# esp32-canbus.net
KiCad netlist of a schematic drawn in EAGLE
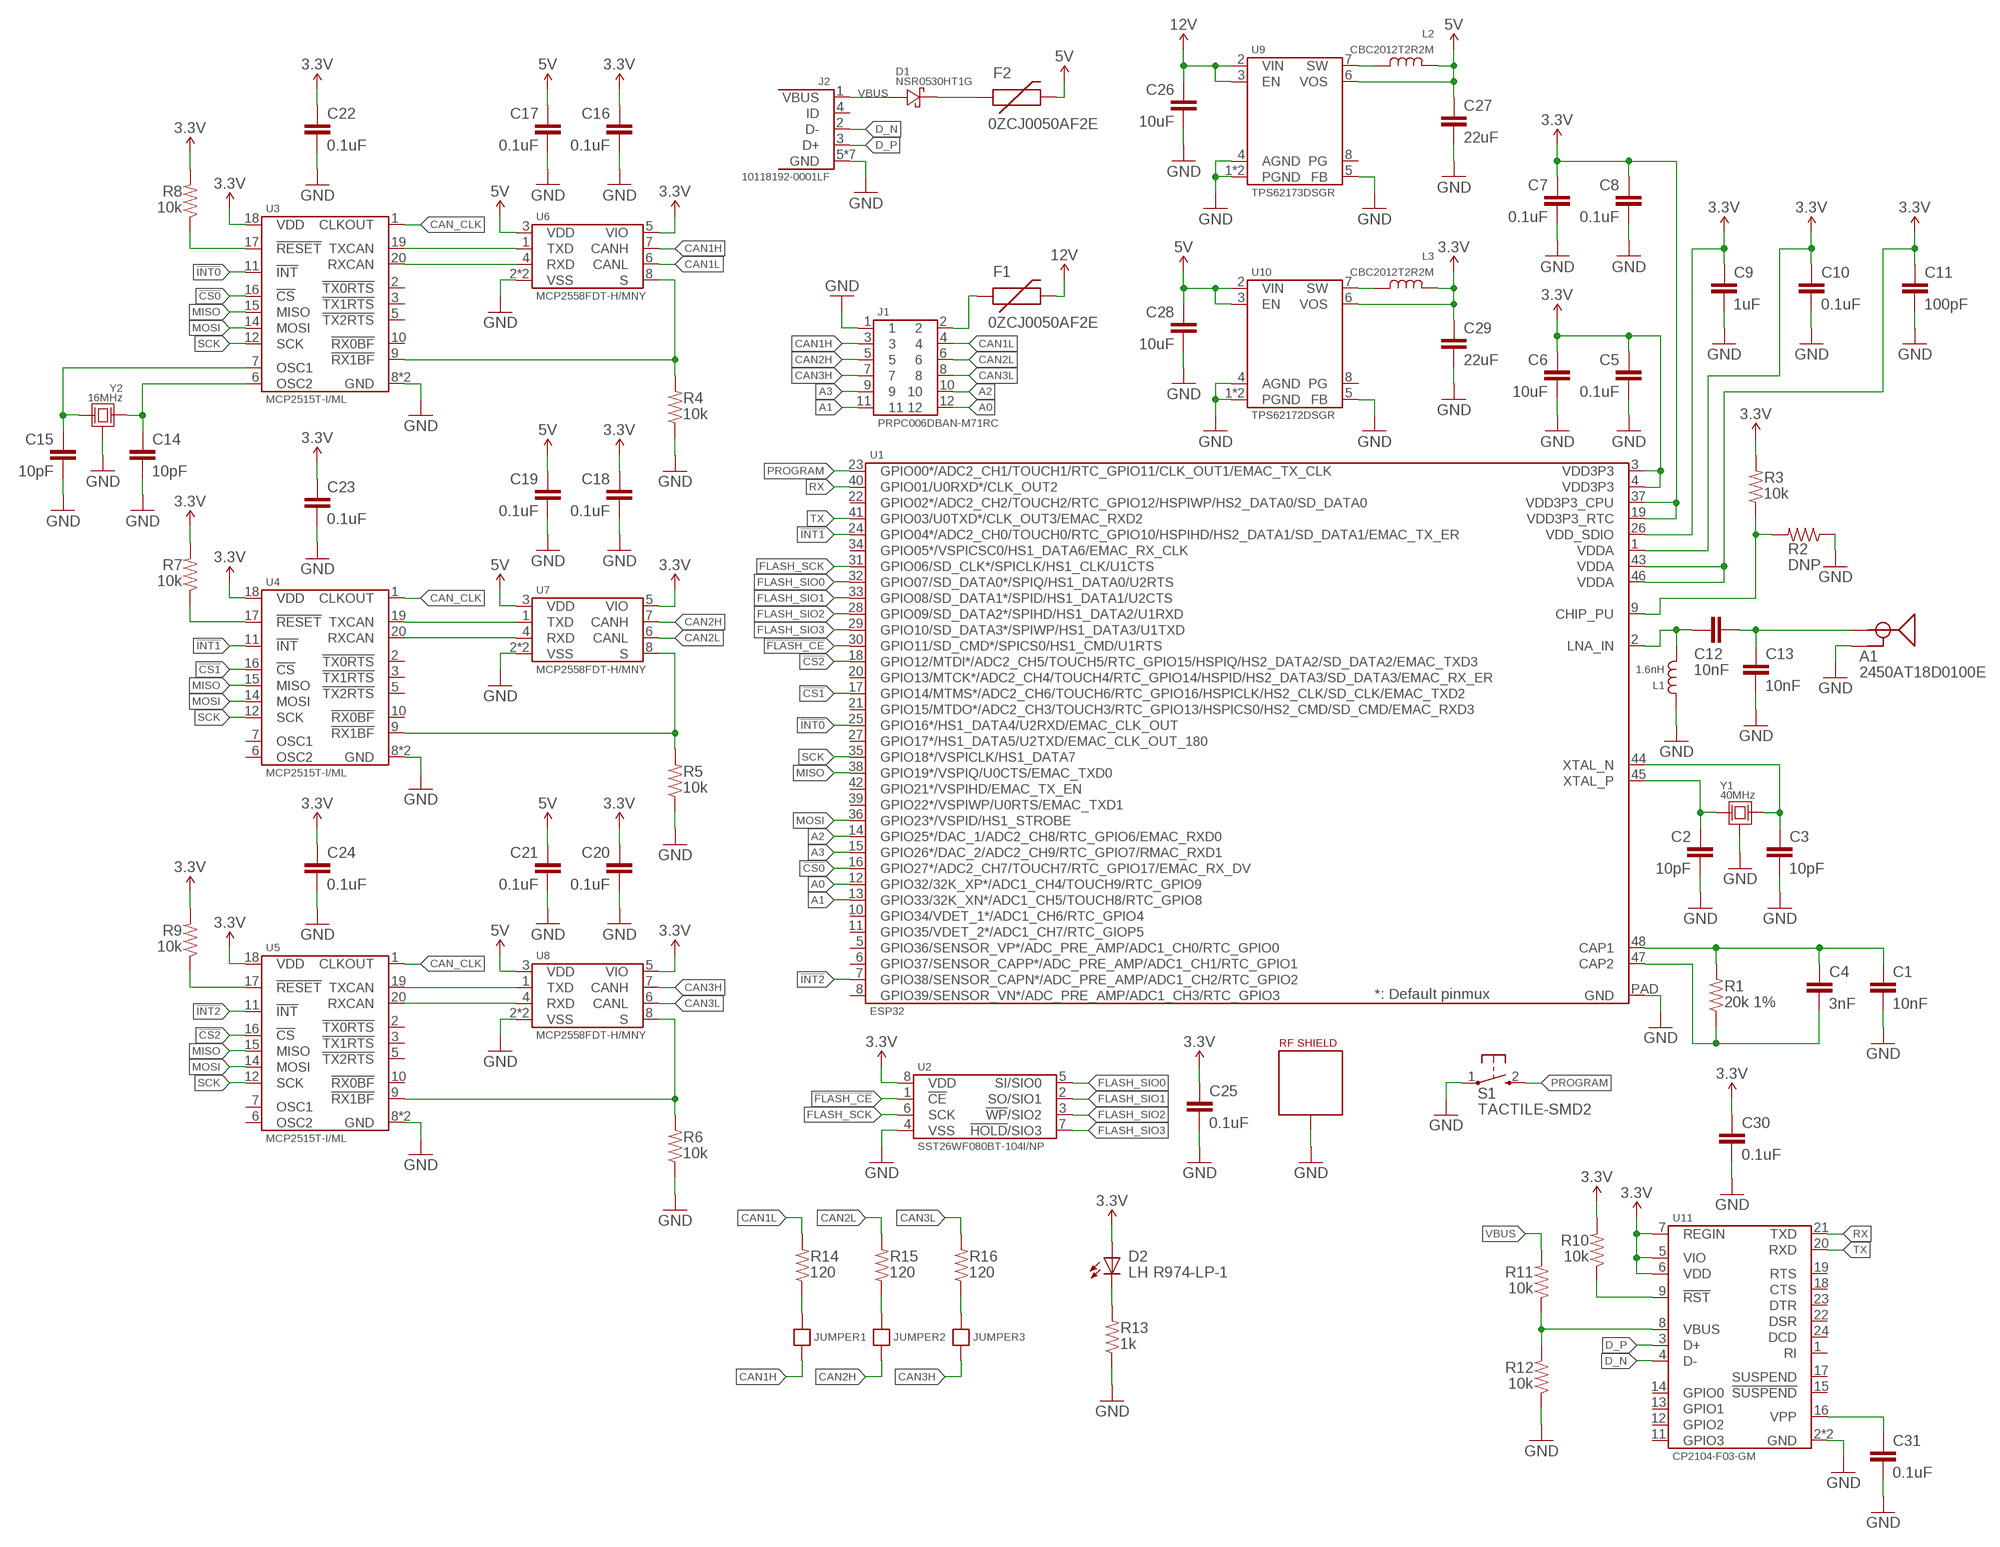
[diagram p0: schematic, sheet 1]

(export (version "E")
  (design (tool "Eeschema 10.0.6"))
  (components
    (comp (ref "A1")
      (value "2450AT18D0100E")
      (footprint "eagle-import:4SMD-ANTENNA")
      (libsource (lib "eagle-import") (part "2450AT18D0100E"))
    )
    (comp (ref "C1")
      (value "10nF")
      (footprint "eagle-import:0603-CAP")
      (libsource (lib "eagle-import") (part "CAP-0603"))
    )
    (comp (ref "C2")
      (value "10pF")
      (footprint "eagle-import:0603-CAP")
      (libsource (lib "eagle-import") (part "CAP-0603"))
    )
    (comp (ref "C3")
      (value "10pF")
      (footprint "eagle-import:0603-CAP")
      (libsource (lib "eagle-import") (part "CAP-0603"))
    )
    (comp (ref "C4")
      (value "3nF")
      (footprint "eagle-import:0603-CAP")
      (libsource (lib "eagle-import") (part "CAP-0603"))
    )
    (comp (ref "C5")
      (value "0.1uF")
      (footprint "eagle-import:0603-CAP")
      (libsource (lib "eagle-import") (part "CAP-0603"))
    )
    (comp (ref "C6")
      (value "10uF")
      (footprint "eagle-import:0603-CAP")
      (libsource (lib "eagle-import") (part "CAP-0603"))
    )
    (comp (ref "C7")
      (value "0.1uF")
      (footprint "eagle-import:0603-CAP")
      (libsource (lib "eagle-import") (part "CAP-0603"))
    )
    (comp (ref "C8")
      (value "0.1uF")
      (footprint "eagle-import:0603-CAP")
      (libsource (lib "eagle-import") (part "CAP-0603"))
    )
    (comp (ref "C9")
      (value "1uF")
      (footprint "eagle-import:0603-CAP")
      (libsource (lib "eagle-import") (part "CAP-0603"))
    )
    (comp (ref "C10")
      (value "0.1uF")
      (footprint "eagle-import:0603-CAP")
      (libsource (lib "eagle-import") (part "CAP-0603"))
    )
    (comp (ref "C11")
      (value "100pF")
      (footprint "eagle-import:0603-CAP")
      (libsource (lib "eagle-import") (part "CAP-0603"))
    )
    (comp (ref "C12")
      (value "10nF")
      (footprint "eagle-import:0603-CAP")
      (libsource (lib "eagle-import") (part "CAP-0603"))
    )
    (comp (ref "C13")
      (value "10nF")
      (footprint "eagle-import:0603-CAP")
      (libsource (lib "eagle-import") (part "CAP-0603"))
    )
    (comp (ref "C14")
      (value "10pF")
      (footprint "eagle-import:0603-CAP")
      (libsource (lib "eagle-import") (part "CAP-0603"))
    )
    (comp (ref "C15")
      (value "10pF")
      (footprint "eagle-import:0603-CAP")
      (libsource (lib "eagle-import") (part "CAP-0603"))
    )
    (comp (ref "C16")
      (value "0.1uF")
      (footprint "eagle-import:0603-CAP")
      (libsource (lib "eagle-import") (part "CAP-0603"))
    )
    (comp (ref "C17")
      (value "0.1uF")
      (footprint "eagle-import:0603-CAP")
      (libsource (lib "eagle-import") (part "CAP-0603"))
    )
    (comp (ref "C18")
      (value "0.1uF")
      (footprint "eagle-import:0603-CAP")
      (libsource (lib "eagle-import") (part "CAP-0603"))
    )
    (comp (ref "C19")
      (value "0.1uF")
      (footprint "eagle-import:0603-CAP")
      (libsource (lib "eagle-import") (part "CAP-0603"))
    )
    (comp (ref "C20")
      (value "0.1uF")
      (footprint "eagle-import:0603-CAP")
      (libsource (lib "eagle-import") (part "CAP-0603"))
    )
    (comp (ref "C21")
      (value "0.1uF")
      (footprint "eagle-import:0603-CAP")
      (libsource (lib "eagle-import") (part "CAP-0603"))
    )
    (comp (ref "C22")
      (value "0.1uF")
      (footprint "eagle-import:0603-CAP")
      (libsource (lib "eagle-import") (part "CAP-0603"))
    )
    (comp (ref "C23")
      (value "0.1uF")
      (footprint "eagle-import:0603-CAP")
      (libsource (lib "eagle-import") (part "CAP-0603"))
    )
    (comp (ref "C24")
      (value "0.1uF")
      (footprint "eagle-import:0603-CAP")
      (libsource (lib "eagle-import") (part "CAP-0603"))
    )
    (comp (ref "C25")
      (value "0.1uF")
      (footprint "eagle-import:0603-CAP")
      (libsource (lib "eagle-import") (part "CAP-0603"))
    )
    (comp (ref "C26")
      (value "10uF")
      (footprint "eagle-import:0603-CAP")
      (libsource (lib "eagle-import") (part "CAP-0603"))
    )
    (comp (ref "C27")
      (value "22uF")
      (footprint "eagle-import:0805-CAP")
      (libsource (lib "eagle-import") (part "CAP-0805"))
    )
    (comp (ref "C28")
      (value "10uF")
      (footprint "eagle-import:0603-CAP")
      (libsource (lib "eagle-import") (part "CAP-0603"))
    )
    (comp (ref "C29")
      (value "22uF")
      (footprint "eagle-import:0805-CAP")
      (libsource (lib "eagle-import") (part "CAP-0805"))
    )
    (comp (ref "C30")
      (value "0.1uF")
      (footprint "eagle-import:0603-CAP")
      (libsource (lib "eagle-import") (part "CAP-0603"))
    )
    (comp (ref "C31")
      (value "0.1uF")
      (footprint "eagle-import:0603-CAP")
      (libsource (lib "eagle-import") (part "CAP-0603"))
    )
    (comp (ref "D1")
      (value "NSR0530HT1G")
      (footprint "eagle-import:SOD323")
      (libsource (lib "eagle-import") (part "NSR0530HT1G"))
    )
    (comp (ref "D2")
      (value "LH R974-LP-1")
      (footprint "eagle-import:0805-LED")
      (libsource (lib "eagle-import") (part "LED-0805"))
    )
    (comp (ref "F1")
      (value "0ZCJ0050AF2E")
      (footprint "eagle-import:1206-PTC")
      (libsource (lib "eagle-import") (part "PTC-1206"))
    )
    (comp (ref "F2")
      (value "0ZCJ0050AF2E")
      (footprint "eagle-import:1206-PTC")
      (libsource (lib "eagle-import") (part "PTC-1206"))
    )
    (comp (ref "J1")
      (value "PRPC006DBAN-M71RC")
      (footprint "eagle-import:M06X2-PTH-H")
      (libsource (lib "eagle-import") (part "M06X2-100MIL-H"))
    )
    (comp (ref "J2")
      (value "10118192-0001LF")
      (footprint "eagle-import:10118192-0001LF")
      (libsource (lib "eagle-import") (part "USB-MICROB-3"))
    )
    (comp (ref "JUMPER1")
      (value "JUMPER-NO")
      (footprint "eagle-import:JUMPER-NO")
      (libsource (lib "eagle-import") (part "JUMPER-NO"))
    )
    (comp (ref "JUMPER2")
      (value "JUMPER-NO")
      (footprint "eagle-import:JUMPER-NO")
      (libsource (lib "eagle-import") (part "JUMPER-NO"))
    )
    (comp (ref "JUMPER3")
      (value "JUMPER-NO")
      (footprint "eagle-import:JUMPER-NO")
      (libsource (lib "eagle-import") (part "JUMPER-NO"))
    )
    (comp (ref "L1")
      (value "1.6nH")
      (footprint "eagle-import:0402-INDUCTOR")
      (libsource (lib "eagle-import") (part "INDUCTOR-0402"))
    )
    (comp (ref "L2")
      (value "CBC2012T2R2M")
      (footprint "eagle-import:0805")
      (libsource (lib "eagle-import") (part "INDUCTOR-0805"))
    )
    (comp (ref "L3")
      (value "CBC2012T2R2M")
      (footprint "eagle-import:0805")
      (libsource (lib "eagle-import") (part "INDUCTOR-0805"))
    )
    (comp (ref "R1")
      (value "20k 1%")
      (footprint "eagle-import:0603-CAP")
      (libsource (lib "eagle-import") (part "RESISTOR-0603"))
    )
    (comp (ref "R2")
      (value "DNP")
      (footprint "eagle-import:0603-CAP")
      (libsource (lib "eagle-import") (part "RESISTOR-0603"))
    )
    (comp (ref "R3")
      (value "10k")
      (footprint "eagle-import:0603-CAP")
      (libsource (lib "eagle-import") (part "RESISTOR-0603"))
    )
    (comp (ref "R4")
      (value "10k")
      (footprint "eagle-import:0603-CAP")
      (libsource (lib "eagle-import") (part "RESISTOR-0603"))
    )
    (comp (ref "R5")
      (value "10k")
      (footprint "eagle-import:0603-CAP")
      (libsource (lib "eagle-import") (part "RESISTOR-0603"))
    )
    (comp (ref "R6")
      (value "10k")
      (footprint "eagle-import:0603-CAP")
      (libsource (lib "eagle-import") (part "RESISTOR-0603"))
    )
    (comp (ref "R7")
      (value "10k")
      (footprint "eagle-import:0603-CAP")
      (libsource (lib "eagle-import") (part "RESISTOR-0603"))
    )
    (comp (ref "R8")
      (value "10k")
      (footprint "eagle-import:0603-CAP")
      (libsource (lib "eagle-import") (part "RESISTOR-0603"))
    )
    (comp (ref "R9")
      (value "10k")
      (footprint "eagle-import:0603-CAP")
      (libsource (lib "eagle-import") (part "RESISTOR-0603"))
    )
    (comp (ref "R10")
      (value "10k")
      (footprint "eagle-import:0603-CAP")
      (libsource (lib "eagle-import") (part "RESISTOR-0603"))
    )
    (comp (ref "R11")
      (value "10k")
      (footprint "eagle-import:0603-CAP")
      (libsource (lib "eagle-import") (part "RESISTOR-0603"))
    )
    (comp (ref "R12")
      (value "10k")
      (footprint "eagle-import:0603-CAP")
      (libsource (lib "eagle-import") (part "RESISTOR-0603"))
    )
    (comp (ref "R13")
      (value "1k")
      (footprint "eagle-import:0603-CAP")
      (libsource (lib "eagle-import") (part "RESISTOR-0603"))
    )
    (comp (ref "R14")
      (value "120")
      (footprint "eagle-import:0603-CAP")
      (libsource (lib "eagle-import") (part "RESISTOR-0603"))
    )
    (comp (ref "R15")
      (value "120")
      (footprint "eagle-import:0603-CAP")
      (libsource (lib "eagle-import") (part "RESISTOR-0603"))
    )
    (comp (ref "R16")
      (value "120")
      (footprint "eagle-import:0603-CAP")
      (libsource (lib "eagle-import") (part "RESISTOR-0603"))
    )
    (comp (ref "S1")
      (value "TACTILE-SMD2")
      (footprint "eagle-import:PTS820-J15M-SMTR-LFS")
      (libsource (lib "eagle-import") (part "TACTILE-SMD2"))
    )
    (comp (ref "SH1")
      (value "BMI-S-102")
      (footprint "eagle-import:RF_SHIELD-.65X.65")
      (libsource (lib "eagle-import") (part "RF-SHIELD"))
    )
    (comp (ref "U1")
      (value "ESP32")
      (footprint "eagle-import:ESP32")
      (libsource (lib "eagle-import") (part "ESP32"))
    )
    (comp (ref "U2")
      (value "SST26WF080BT-104I/NP")
      (footprint "eagle-import:USON-8-2X3")
      (libsource (lib "eagle-import") (part "FLASH-USON"))
    )
    (comp (ref "U3")
      (value "MCP2515T-I/ML")
      (footprint "eagle-import:VQFN-20-4MM")
      (libsource (lib "eagle-import") (part "MCP2515T-I/ML"))
    )
    (comp (ref "U4")
      (value "MCP2515T-I/ML")
      (footprint "eagle-import:VQFN-20-4MM")
      (libsource (lib "eagle-import") (part "MCP2515T-I/ML"))
    )
    (comp (ref "U5")
      (value "MCP2515T-I/ML")
      (footprint "eagle-import:VQFN-20-4MM")
      (libsource (lib "eagle-import") (part "MCP2515T-I/ML"))
    )
    (comp (ref "U6")
      (value "MCP2558FDT-H/MNY")
      (footprint "eagle-import:TDFN-8-2X3")
      (libsource (lib "eagle-import") (part "MCP2558FDT-H/MNY"))
    )
    (comp (ref "U7")
      (value "MCP2558FDT-H/MNY")
      (footprint "eagle-import:TDFN-8-2X3")
      (libsource (lib "eagle-import") (part "MCP2558FDT-H/MNY"))
    )
    (comp (ref "U8")
      (value "MCP2558FDT-H/MNY")
      (footprint "eagle-import:TDFN-8-2X3")
      (libsource (lib "eagle-import") (part "MCP2558FDT-H/MNY"))
    )
    (comp (ref "U9")
      (value "TPS62173DSGR")
      (footprint "eagle-import:DFN-8-2MM")
      (libsource (lib "eagle-import") (part "TPS62173DSGR"))
    )
    (comp (ref "U10")
      (value "TPS62172DSGR")
      (footprint "eagle-import:DFN-8-2MM")
      (libsource (lib "eagle-import") (part "TPS62172DSGR"))
    )
    (comp (ref "U11")
      (value "CP2104-F03-GM")
      (footprint "eagle-import:QFN-24-4X4")
      (libsource (lib "eagle-import") (part "CP2104-F03-GM"))
    )
    (comp (ref "Y1")
      (value "40MHz")
      (footprint "eagle-import:FA-238")
      (libsource (lib "eagle-import") (part "CRYSTAL-3.2X2.5"))
    )
    (comp (ref "Y2")
      (value "16MHz")
      (footprint "eagle-import:FA-238")
      (libsource (lib "eagle-import") (part "CRYSTAL-3.2X2.5"))
    )
  )
  (nets
    (net (code "1") (name "/~{CS0}") (class "Default")
      (node (ref "U1") (pin "16") (pinfunction "GPIO27*/ADC2_CH7/TOUCH7/RTC_GPIO17/EMAC_RX_DV_16") (pintype "bidirectional"))
      (node (ref "U3") (pin "16") (pinfunction "~{CS}_16") (pintype "bidirectional"))
    )
    (net (code "2") (name "/~{CS1}") (class "Default")
      (node (ref "U1") (pin "17") (pinfunction "GPIO14/MTMS*/ADC2_CH6/TOUCH6/RTC_GPIO16/HSPICLK/HS2_CLK/SD_CLK/EMAC_TXD2_17") (pintype "bidirectional"))
      (node (ref "U4") (pin "16") (pinfunction "~{CS}_16") (pintype "bidirectional"))
    )
    (net (code "3") (name "/~{CS2}") (class "Default")
      (node (ref "U1") (pin "18") (pinfunction "GPIO12/MTDI*/ADC2_CH5/TOUCH5/RTC_GPIO15/HSPIQ/HS2_DATA2/SD_DATA2/EMAC_TXD3_18") (pintype "bidirectional"))
      (node (ref "U5") (pin "16") (pinfunction "~{CS}_16") (pintype "bidirectional"))
    )
    (net (code "4") (name "/~{FLASH_CE}") (class "Default")
      (node (ref "U1") (pin "30") (pinfunction "GPIO11/SD_CMD*/SPICS0/HS1_CMD/U1RTS_30") (pintype "bidirectional"))
      (node (ref "U2") (pin "1") (pinfunction "~{CE}_1") (pintype "bidirectional"))
    )
    (net (code "5") (name "/~{INT0}") (class "Default")
      (node (ref "U1") (pin "25") (pinfunction "GPIO16*/HS1_DATA4/U2RXD/EMAC_CLK_OUT_25") (pintype "bidirectional"))
      (node (ref "U3") (pin "11") (pinfunction "~{INT}_11") (pintype "bidirectional"))
    )
    (net (code "6") (name "/~{INT1}") (class "Default")
      (node (ref "U1") (pin "24") (pinfunction "GPIO04*/ADC2_CH0/TOUCH0/RTC_GPIO10/HSPIHD/HS2_DATA1/SD_DATA1/EMAC_TX_ER_24") (pintype "bidirectional"))
      (node (ref "U4") (pin "11") (pinfunction "~{INT}_11") (pintype "bidirectional"))
    )
    (net (code "7") (name "/~{INT2}") (class "Default")
      (node (ref "U1") (pin "7") (pinfunction "GPIO38/SENSOR_CAPN*/ADC_PRE_AMP/ADC1_CH2/RTC_GPIO2_7") (pintype "bidirectional"))
      (node (ref "U5") (pin "11") (pinfunction "~{INT}_11") (pintype "bidirectional"))
    )
    (net (code "8") (name "3.3V") (class "Default")
      (node (ref "C10") (pin "1") (pinfunction "1_1") (pintype "passive"))
      (node (ref "C11") (pin "1") (pinfunction "1_1") (pintype "passive"))
      (node (ref "C16") (pin "1") (pinfunction "1_1") (pintype "passive"))
      (node (ref "C18") (pin "1") (pinfunction "1_1") (pintype "passive"))
      (node (ref "C20") (pin "1") (pinfunction "1_1") (pintype "passive"))
      (node (ref "C22") (pin "1") (pinfunction "1_1") (pintype "passive"))
      (node (ref "C23") (pin "1") (pinfunction "1_1") (pintype "passive"))
      (node (ref "C24") (pin "1") (pinfunction "1_1") (pintype "passive"))
      (node (ref "C25") (pin "1") (pinfunction "1_1") (pintype "passive"))
      (node (ref "C29") (pin "1") (pinfunction "1_1") (pintype "passive"))
      (node (ref "C30") (pin "1") (pinfunction "1_1") (pintype "passive"))
      (node (ref "C5") (pin "1") (pinfunction "1_1") (pintype "passive"))
      (node (ref "C6") (pin "1") (pinfunction "1_1") (pintype "passive"))
      (node (ref "C7") (pin "1") (pinfunction "1_1") (pintype "passive"))
      (node (ref "C8") (pin "1") (pinfunction "1_1") (pintype "passive"))
      (node (ref "C9") (pin "1") (pinfunction "1_1") (pintype "passive"))
      (node (ref "D2") (pin "A") (pinfunction "A_A") (pintype "passive"))
      (node (ref "L3") (pin "2") (pinfunction "P$2_2") (pintype "bidirectional"))
      (node (ref "R10") (pin "2") (pinfunction "2_2") (pintype "passive"))
      (node (ref "R3") (pin "2") (pinfunction "2_2") (pintype "passive"))
      (node (ref "R7") (pin "2") (pinfunction "2_2") (pintype "passive"))
      (node (ref "R8") (pin "2") (pinfunction "2_2") (pintype "passive"))
      (node (ref "R9") (pin "2") (pinfunction "2_2") (pintype "passive"))
      (node (ref "U1") (pin "1") (pinfunction "VDDA_1") (pintype "bidirectional"))
      (node (ref "U1") (pin "19") (pinfunction "VDD3P3_RTC_19") (pintype "bidirectional"))
      (node (ref "U1") (pin "26") (pinfunction "VDD_SDIO_26") (pintype "bidirectional"))
      (node (ref "U1") (pin "3") (pinfunction "VDD3P3_3") (pintype "bidirectional"))
      (node (ref "U1") (pin "37") (pinfunction "VDD3P3_CPU_37") (pintype "bidirectional"))
      (node (ref "U1") (pin "4") (pinfunction "VDD3P3_4") (pintype "bidirectional"))
      (node (ref "U1") (pin "43") (pinfunction "VDDA_43") (pintype "bidirectional"))
      (node (ref "U1") (pin "46") (pinfunction "VDDA_46") (pintype "bidirectional"))
      (node (ref "U10") (pin "6") (pinfunction "VOS_6") (pintype "bidirectional"))
      (node (ref "U11") (pin "5") (pinfunction "VIO_5") (pintype "bidirectional"))
      (node (ref "U11") (pin "6") (pinfunction "VDD_6") (pintype "bidirectional"))
      (node (ref "U11") (pin "7") (pinfunction "REGIN_7") (pintype "bidirectional"))
      (node (ref "U2") (pin "8") (pinfunction "VDD_8") (pintype "bidirectional"))
      (node (ref "U3") (pin "18") (pinfunction "VDD_18") (pintype "bidirectional"))
      (node (ref "U4") (pin "18") (pinfunction "VDD_18") (pintype "bidirectional"))
      (node (ref "U5") (pin "18") (pinfunction "VDD_18") (pintype "bidirectional"))
      (node (ref "U6") (pin "5") (pinfunction "VIO_5") (pintype "bidirectional"))
      (node (ref "U7") (pin "5") (pinfunction "VIO_5") (pintype "bidirectional"))
      (node (ref "U8") (pin "5") (pinfunction "VIO_5") (pintype "bidirectional"))
    )
    (net (code "9") (name "5V") (class "Default")
      (node (ref "C17") (pin "1") (pinfunction "1_1") (pintype "passive"))
      (node (ref "C19") (pin "1") (pinfunction "1_1") (pintype "passive"))
      (node (ref "C21") (pin "1") (pinfunction "1_1") (pintype "passive"))
      (node (ref "C27") (pin "1") (pinfunction "1_1") (pintype "passive"))
      (node (ref "C28") (pin "1") (pinfunction "1_1") (pintype "passive"))
      (node (ref "F2") (pin "P$2") (pinfunction "2_P$2") (pintype "bidirectional"))
      (node (ref "L2") (pin "2") (pinfunction "P$2_2") (pintype "bidirectional"))
      (node (ref "U10") (pin "2") (pinfunction "VIN_2") (pintype "bidirectional"))
      (node (ref "U10") (pin "3") (pinfunction "EN_3") (pintype "bidirectional"))
      (node (ref "U6") (pin "3") (pinfunction "VDD_3") (pintype "bidirectional"))
      (node (ref "U7") (pin "3") (pinfunction "VDD_3") (pintype "bidirectional"))
      (node (ref "U8") (pin "3") (pinfunction "VDD_3") (pintype "bidirectional"))
      (node (ref "U9") (pin "6") (pinfunction "VOS_6") (pintype "bidirectional"))
    )
    (net (code "10") (name "12V") (class "Default")
      (node (ref "C26") (pin "1") (pinfunction "1_1") (pintype "passive"))
      (node (ref "F1") (pin "P$2") (pinfunction "2_P$2") (pintype "bidirectional"))
      (node (ref "U9") (pin "2") (pinfunction "VIN_2") (pintype "bidirectional"))
      (node (ref "U9") (pin "3") (pinfunction "EN_3") (pintype "bidirectional"))
    )
    (net (code "11") (name "A0") (class "Default")
      (node (ref "J1") (pin "12") (pinfunction "12_12") (pintype "bidirectional"))
      (node (ref "U1") (pin "12") (pinfunction "GPIO32/32K_XP*/ADC1_CH4/TOUCH9/RTC_GPIO9_12") (pintype "bidirectional"))
    )
    (net (code "12") (name "A1") (class "Default")
      (node (ref "J1") (pin "11") (pinfunction "11_11") (pintype "bidirectional"))
      (node (ref "U1") (pin "13") (pinfunction "GPIO33/32K_XN*/ADC1_CH5/TOUCH8/RTC_GPIO8_13") (pintype "bidirectional"))
    )
    (net (code "13") (name "A2") (class "Default")
      (node (ref "J1") (pin "10") (pinfunction "10_10") (pintype "bidirectional"))
      (node (ref "U1") (pin "14") (pinfunction "GPIO25*/DAC_1/ADC2_CH8/RTC_GPIO6/EMAC_RXD0_14") (pintype "bidirectional"))
    )
    (net (code "14") (name "A3") (class "Default")
      (node (ref "J1") (pin "9") (pinfunction "9_9") (pintype "bidirectional"))
      (node (ref "U1") (pin "15") (pinfunction "GPIO26*/DAC_2/ADC2_CH9/RTC_GPIO7/RMAC_RXD1_15") (pintype "bidirectional"))
    )
    (net (code "15") (name "CAN1H") (class "Default")
      (node (ref "J1") (pin "3") (pinfunction "3_3") (pintype "bidirectional"))
      (node (ref "JUMPER1") (pin "P$1") (pinfunction "P$1_P$1") (pintype "bidirectional"))
      (node (ref "U6") (pin "7") (pinfunction "CANH_7") (pintype "bidirectional"))
    )
    (net (code "16") (name "CAN1L") (class "Default")
      (node (ref "J1") (pin "4") (pinfunction "4_4") (pintype "bidirectional"))
      (node (ref "R14") (pin "2") (pinfunction "2_2") (pintype "passive"))
      (node (ref "U6") (pin "6") (pinfunction "CANL_6") (pintype "bidirectional"))
    )
    (net (code "17") (name "CAN2H") (class "Default")
      (node (ref "J1") (pin "5") (pinfunction "5_5") (pintype "bidirectional"))
      (node (ref "JUMPER2") (pin "P$1") (pinfunction "P$1_P$1") (pintype "bidirectional"))
      (node (ref "U7") (pin "7") (pinfunction "CANH_7") (pintype "bidirectional"))
    )
    (net (code "18") (name "CAN2L") (class "Default")
      (node (ref "J1") (pin "6") (pinfunction "6_6") (pintype "bidirectional"))
      (node (ref "R15") (pin "2") (pinfunction "2_2") (pintype "passive"))
      (node (ref "U7") (pin "6") (pinfunction "CANL_6") (pintype "bidirectional"))
    )
    (net (code "19") (name "CAN3H") (class "Default")
      (node (ref "J1") (pin "7") (pinfunction "7_7") (pintype "bidirectional"))
      (node (ref "JUMPER3") (pin "P$1") (pinfunction "P$1_P$1") (pintype "bidirectional"))
      (node (ref "U8") (pin "7") (pinfunction "CANH_7") (pintype "bidirectional"))
    )
    (net (code "20") (name "CAN3L") (class "Default")
      (node (ref "J1") (pin "8") (pinfunction "8_8") (pintype "bidirectional"))
      (node (ref "R16") (pin "2") (pinfunction "2_2") (pintype "passive"))
      (node (ref "U8") (pin "6") (pinfunction "CANL_6") (pintype "bidirectional"))
    )
    (net (code "21") (name "CAN_CLK") (class "Default")
      (node (ref "U3") (pin "1") (pinfunction "CLKOUT_1") (pintype "bidirectional"))
      (node (ref "U4") (pin "1") (pinfunction "CLKOUT_1") (pintype "bidirectional"))
      (node (ref "U5") (pin "1") (pinfunction "CLKOUT_1") (pintype "bidirectional"))
    )
    (net (code "22") (name "D_N") (class "Default")
      (node (ref "J2") (pin "2") (pinfunction "D-_2") (pintype "bidirectional"))
      (node (ref "U11") (pin "4") (pinfunction "D-_4") (pintype "bidirectional"))
    )
    (net (code "23") (name "D_P") (class "Default")
      (node (ref "J2") (pin "3") (pinfunction "D+_3") (pintype "bidirectional"))
      (node (ref "U11") (pin "3") (pinfunction "D+_3") (pintype "bidirectional"))
    )
    (net (code "24") (name "FLASH_SCK") (class "Default")
      (node (ref "U1") (pin "31") (pinfunction "GPIO06/SD_CLK*/SPICLK/HS1_CLK/U1CTS_31") (pintype "bidirectional"))
      (node (ref "U2") (pin "6") (pinfunction "SCK_6") (pintype "bidirectional"))
    )
    (net (code "25") (name "FLASH_SIO0") (class "Default")
      (node (ref "U1") (pin "32") (pinfunction "GPIO07/SD_DATA0*/SPIQ/HS1_DATA0/U2RTS_32") (pintype "bidirectional"))
      (node (ref "U2") (pin "5") (pinfunction "SI/SIO0_5") (pintype "bidirectional"))
    )
    (net (code "26") (name "FLASH_SIO1") (class "Default")
      (node (ref "U1") (pin "33") (pinfunction "GPIO08/SD_DATA1*/SPID/HS1_DATA1/U2CTS_33") (pintype "bidirectional"))
      (node (ref "U2") (pin "2") (pinfunction "SO/SIO1_2") (pintype "bidirectional"))
    )
    (net (code "27") (name "FLASH_SIO2") (class "Default")
      (node (ref "U1") (pin "28") (pinfunction "GPIO09/SD_DATA2*/SPIHD/HS1_DATA2/U1RXD_28") (pintype "bidirectional"))
      (node (ref "U2") (pin "3") (pinfunction "~{WP}/SIO2_3") (pintype "bidirectional"))
    )
    (net (code "28") (name "FLASH_SIO3") (class "Default")
      (node (ref "U1") (pin "29") (pinfunction "GPIO10/SD_DATA3*/SPIWP/HS1_DATA3/U1TXD_29") (pintype "bidirectional"))
      (node (ref "U2") (pin "7") (pinfunction "~{HOLD}/SIO3_7") (pintype "bidirectional"))
    )
    (net (code "29") (name "GND") (class "Default")
      (node (ref "A1") (pin "2") (pinfunction "GND_2") (pintype "bidirectional"))
      (node (ref "A1") (pin "3") (pinfunction "GND_3") (pintype "bidirectional"))
      (node (ref "A1") (pin "4") (pinfunction "GND_4") (pintype "bidirectional"))
      (node (ref "C1") (pin "2") (pinfunction "2_2") (pintype "passive"))
      (node (ref "C10") (pin "2") (pinfunction "2_2") (pintype "passive"))
      (node (ref "C11") (pin "2") (pinfunction "2_2") (pintype "passive"))
      (node (ref "C13") (pin "2") (pinfunction "2_2") (pintype "passive"))
      (node (ref "C14") (pin "2") (pinfunction "2_2") (pintype "passive"))
      (node (ref "C15") (pin "2") (pinfunction "2_2") (pintype "passive"))
      (node (ref "C16") (pin "2") (pinfunction "2_2") (pintype "passive"))
      (node (ref "C17") (pin "2") (pinfunction "2_2") (pintype "passive"))
      (node (ref "C18") (pin "2") (pinfunction "2_2") (pintype "passive"))
      (node (ref "C19") (pin "2") (pinfunction "2_2") (pintype "passive"))
      (node (ref "C2") (pin "2") (pinfunction "2_2") (pintype "passive"))
      (node (ref "C20") (pin "2") (pinfunction "2_2") (pintype "passive"))
      (node (ref "C21") (pin "2") (pinfunction "2_2") (pintype "passive"))
      (node (ref "C22") (pin "2") (pinfunction "2_2") (pintype "passive"))
      (node (ref "C23") (pin "2") (pinfunction "2_2") (pintype "passive"))
      (node (ref "C24") (pin "2") (pinfunction "2_2") (pintype "passive"))
      (node (ref "C25") (pin "2") (pinfunction "2_2") (pintype "passive"))
      (node (ref "C26") (pin "2") (pinfunction "2_2") (pintype "passive"))
      (node (ref "C27") (pin "2") (pinfunction "2_2") (pintype "passive"))
      (node (ref "C28") (pin "2") (pinfunction "2_2") (pintype "passive"))
      (node (ref "C29") (pin "2") (pinfunction "2_2") (pintype "passive"))
      (node (ref "C3") (pin "2") (pinfunction "2_2") (pintype "passive"))
      (node (ref "C30") (pin "2") (pinfunction "2_2") (pintype "passive"))
      (node (ref "C31") (pin "2") (pinfunction "2_2") (pintype "passive"))
      (node (ref "C5") (pin "2") (pinfunction "2_2") (pintype "passive"))
      (node (ref "C6") (pin "2") (pinfunction "2_2") (pintype "passive"))
      (node (ref "C7") (pin "2") (pinfunction "2_2") (pintype "passive"))
      (node (ref "C8") (pin "2") (pinfunction "2_2") (pintype "passive"))
      (node (ref "C9") (pin "2") (pinfunction "2_2") (pintype "passive"))
      (node (ref "J1") (pin "1") (pinfunction "1_1") (pintype "bidirectional"))
      (node (ref "J2") (pin "5") (pinfunction "GND_5") (pintype "bidirectional"))
      (node (ref "J2") (pin "P$10") (pinfunction "GND_P$10") (pintype "bidirectional"))
      (node (ref "J2") (pin "P$11") (pinfunction "GND_P$11") (pintype "bidirectional"))
      (node (ref "J2") (pin "P$6") (pinfunction "GND_P$6") (pintype "bidirectional"))
      (node (ref "J2") (pin "P$7") (pinfunction "GND_P$7") (pintype "bidirectional"))
      (node (ref "J2") (pin "P$8") (pinfunction "GND_P$8") (pintype "bidirectional"))
      (node (ref "J2") (pin "P$9") (pinfunction "GND_P$9") (pintype "bidirectional"))
      (node (ref "L1") (pin "1") (pinfunction "P$1_1") (pintype "bidirectional"))
      (node (ref "R12") (pin "1") (pinfunction "1_1") (pintype "passive"))
      (node (ref "R13") (pin "1") (pinfunction "1_1") (pintype "passive"))
      (node (ref "R2") (pin "1") (pinfunction "1_1") (pintype "passive"))
      (node (ref "R4") (pin "1") (pinfunction "1_1") (pintype "passive"))
      (node (ref "R5") (pin "1") (pinfunction "1_1") (pintype "passive"))
      (node (ref "R6") (pin "1") (pinfunction "1_1") (pintype "passive"))
      (node (ref "S1") (pin "1") (pinfunction "1_1") (pintype "passive"))
      (node (ref "SH1") (pin "P$1") (pinfunction "P$1_P$1") (pintype "bidirectional"))
      (node (ref "SH1") (pin "P$10") (pinfunction "P$1_P$10") (pintype "bidirectional"))
      (node (ref "SH1") (pin "P$11") (pinfunction "P$1_P$11") (pintype "bidirectional"))
      (node (ref "SH1") (pin "P$12") (pinfunction "P$1_P$12") (pintype "bidirectional"))
      (node (ref "SH1") (pin "P$2") (pinfunction "P$1_P$2") (pintype "bidirectional"))
      (node (ref "SH1") (pin "P$3") (pinfunction "P$1_P$3") (pintype "bidirectional"))
      (node (ref "SH1") (pin "P$4") (pinfunction "P$1_P$4") (pintype "bidirectional"))
      (node (ref "SH1") (pin "P$5") (pinfunction "P$1_P$5") (pintype "bidirectional"))
      (node (ref "SH1") (pin "P$6") (pinfunction "P$1_P$6") (pintype "bidirectional"))
      (node (ref "SH1") (pin "P$7") (pinfunction "P$1_P$7") (pintype "bidirectional"))
      (node (ref "SH1") (pin "P$8") (pinfunction "P$1_P$8") (pintype "bidirectional"))
      (node (ref "SH1") (pin "P$9") (pinfunction "P$1_P$9") (pintype "bidirectional"))
      (node (ref "U1") (pin "PAD") (pinfunction "GND_PAD") (pintype "bidirectional"))
      (node (ref "U10") (pin "1") (pinfunction "PGND_1") (pintype "bidirectional"))
      (node (ref "U10") (pin "4") (pinfunction "AGND_4") (pintype "bidirectional"))
      (node (ref "U10") (pin "5") (pinfunction "FB_5") (pintype "bidirectional"))
      (node (ref "U10") (pin "PAD") (pinfunction "PGND_PAD") (pintype "bidirectional"))
      (node (ref "U11") (pin "2") (pinfunction "GND_2") (pintype "bidirectional"))
      (node (ref "U11") (pin "PAD") (pinfunction "GND_PAD") (pintype "bidirectional"))
      (node (ref "U2") (pin "4") (pinfunction "VSS_4") (pintype "bidirectional"))
      (node (ref "U3") (pin "8") (pinfunction "GND_8") (pintype "bidirectional"))
      (node (ref "U3") (pin "PAD") (pinfunction "GND_PAD") (pintype "bidirectional"))
      (node (ref "U4") (pin "8") (pinfunction "GND_8") (pintype "bidirectional"))
      (node (ref "U4") (pin "PAD") (pinfunction "GND_PAD") (pintype "bidirectional"))
      (node (ref "U5") (pin "8") (pinfunction "GND_8") (pintype "bidirectional"))
      (node (ref "U5") (pin "PAD") (pinfunction "GND_PAD") (pintype "bidirectional"))
      (node (ref "U6") (pin "2") (pinfunction "VSS_2") (pintype "bidirectional"))
      (node (ref "U6") (pin "PAD") (pinfunction "VSS_PAD") (pintype "bidirectional"))
      (node (ref "U7") (pin "2") (pinfunction "VSS_2") (pintype "bidirectional"))
      (node (ref "U7") (pin "PAD") (pinfunction "VSS_PAD") (pintype "bidirectional"))
      (node (ref "U8") (pin "2") (pinfunction "VSS_2") (pintype "bidirectional"))
      (node (ref "U8") (pin "PAD") (pinfunction "VSS_PAD") (pintype "bidirectional"))
      (node (ref "U9") (pin "1") (pinfunction "PGND_1") (pintype "bidirectional"))
      (node (ref "U9") (pin "4") (pinfunction "AGND_4") (pintype "bidirectional"))
      (node (ref "U9") (pin "5") (pinfunction "FB_5") (pintype "bidirectional"))
      (node (ref "U9") (pin "PAD") (pinfunction "PGND_PAD") (pintype "bidirectional"))
      (node (ref "Y1") (pin "2") (pinfunction "GND_2") (pintype "bidirectional"))
      (node (ref "Y1") (pin "4") (pinfunction "GND_4") (pintype "bidirectional"))
      (node (ref "Y2") (pin "2") (pinfunction "GND_2") (pintype "bidirectional"))
      (node (ref "Y2") (pin "4") (pinfunction "GND_4") (pintype "bidirectional"))
    )
    (net (code "30") (name "MISO") (class "Default")
      (node (ref "U1") (pin "38") (pinfunction "GPIO19*/VSPIQ/U0CTS/EMAC_TXD0_38") (pintype "bidirectional"))
      (node (ref "U3") (pin "15") (pinfunction "MISO_15") (pintype "bidirectional"))
      (node (ref "U4") (pin "15") (pinfunction "MISO_15") (pintype "bidirectional"))
      (node (ref "U5") (pin "15") (pinfunction "MISO_15") (pintype "bidirectional"))
    )
    (net (code "31") (name "MOSI") (class "Default")
      (node (ref "U1") (pin "36") (pinfunction "GPIO23*/VSPID/HS1_STROBE_36") (pintype "bidirectional"))
      (node (ref "U3") (pin "14") (pinfunction "MOSI_14") (pintype "bidirectional"))
      (node (ref "U4") (pin "14") (pinfunction "MOSI_14") (pintype "bidirectional"))
      (node (ref "U5") (pin "14") (pinfunction "MOSI_14") (pintype "bidirectional"))
    )
    (net (code "32") (name "Net-(A1-SIGNAL)") (class "Default")
      (node (ref "A1") (pin "1") (pinfunction "SIGNAL_1") (pintype "bidirectional"))
      (node (ref "C12") (pin "2") (pinfunction "2_2") (pintype "passive"))
      (node (ref "C13") (pin "1") (pinfunction "1_1") (pintype "passive"))
    )
    (net (code "33") (name "Net-(D2-PadC)") (class "Default")
      (node (ref "D2") (pin "C") (pinfunction "C_C") (pintype "passive"))
      (node (ref "R13") (pin "2") (pinfunction "2_2") (pintype "passive"))
    )
    (net (code "34") (name "Net-(F1-1)") (class "Default")
      (node (ref "F1") (pin "P$1") (pinfunction "1_P$1") (pintype "bidirectional"))
      (node (ref "J1") (pin "2") (pinfunction "2_2") (pintype "bidirectional"))
    )
    (net (code "35") (name "Net-(F2-1)") (class "Default")
      (node (ref "D1") (pin "C") (pinfunction "C_C") (pintype "bidirectional"))
      (node (ref "F2") (pin "P$1") (pinfunction "1_P$1") (pintype "bidirectional"))
    )
    (net (code "36") (name "Net-(JUMPER1-PadP$2)") (class "Default")
      (node (ref "JUMPER1") (pin "P$2") (pinfunction "P$2_P$2") (pintype "bidirectional"))
      (node (ref "R14") (pin "1") (pinfunction "1_1") (pintype "passive"))
    )
    (net (code "37") (name "Net-(JUMPER2-PadP$2)") (class "Default")
      (node (ref "JUMPER2") (pin "P$2") (pinfunction "P$2_P$2") (pintype "bidirectional"))
      (node (ref "R15") (pin "1") (pinfunction "1_1") (pintype "passive"))
    )
    (net (code "38") (name "Net-(JUMPER3-PadP$2)") (class "Default")
      (node (ref "JUMPER3") (pin "P$2") (pinfunction "P$2_P$2") (pintype "bidirectional"))
      (node (ref "R16") (pin "1") (pinfunction "1_1") (pintype "passive"))
    )
    (net (code "39") (name "Net-(L1-P$2)") (class "Default")
      (node (ref "C12") (pin "1") (pinfunction "1_1") (pintype "passive"))
      (node (ref "L1") (pin "2") (pinfunction "P$2_2") (pintype "bidirectional"))
      (node (ref "U1") (pin "2") (pinfunction "LNA_IN_2") (pintype "bidirectional"))
    )
    (net (code "40") (name "Net-(L2-P$1)") (class "Default")
      (node (ref "L2") (pin "1") (pinfunction "P$1_1") (pintype "bidirectional"))
      (node (ref "U9") (pin "7") (pinfunction "SW_7") (pintype "bidirectional"))
    )
    (net (code "41") (name "Net-(L3-P$1)") (class "Default")
      (node (ref "L3") (pin "1") (pinfunction "P$1_1") (pintype "bidirectional"))
      (node (ref "U10") (pin "7") (pinfunction "SW_7") (pintype "bidirectional"))
    )
    (net (code "42") (name "Net-(U1-CAP1)") (class "Default")
      (node (ref "C1") (pin "1") (pinfunction "1_1") (pintype "passive"))
      (node (ref "C4") (pin "1") (pinfunction "1_1") (pintype "passive"))
      (node (ref "R1") (pin "2") (pinfunction "2_2") (pintype "passive"))
      (node (ref "U1") (pin "48") (pinfunction "CAP1_48") (pintype "bidirectional"))
    )
    (net (code "43") (name "Net-(U1-CAP2)") (class "Default")
      (node (ref "C4") (pin "2") (pinfunction "2_2") (pintype "passive"))
      (node (ref "R1") (pin "1") (pinfunction "1_1") (pintype "passive"))
      (node (ref "U1") (pin "47") (pinfunction "CAP2_47") (pintype "bidirectional"))
    )
    (net (code "44") (name "Net-(U1-CHIP_PU)") (class "Default")
      (node (ref "R2") (pin "2") (pinfunction "2_2") (pintype "passive"))
      (node (ref "R3") (pin "1") (pinfunction "1_1") (pintype "passive"))
      (node (ref "U1") (pin "9") (pinfunction "CHIP_PU_9") (pintype "bidirectional"))
    )
    (net (code "45") (name "Net-(U1-XTAL_N)") (class "Default")
      (node (ref "C3") (pin "1") (pinfunction "1_1") (pintype "passive"))
      (node (ref "U1") (pin "44") (pinfunction "XTAL_N_44") (pintype "bidirectional"))
      (node (ref "Y1") (pin "3") (pinfunction "2_3") (pintype "bidirectional"))
    )
    (net (code "46") (name "Net-(U1-XTAL_P)") (class "Default")
      (node (ref "C2") (pin "1") (pinfunction "1_1") (pintype "passive"))
      (node (ref "U1") (pin "45") (pinfunction "XTAL_P_45") (pintype "bidirectional"))
      (node (ref "Y1") (pin "1") (pinfunction "1_1") (pintype "bidirectional"))
    )
    (net (code "47") (name "Net-(U3-OSC1)") (class "Default")
      (node (ref "C15") (pin "1") (pinfunction "1_1") (pintype "passive"))
      (node (ref "U3") (pin "7") (pinfunction "OSC1_7") (pintype "bidirectional"))
      (node (ref "Y2") (pin "3") (pinfunction "2_3") (pintype "bidirectional"))
    )
    (net (code "48") (name "Net-(U3-OSC2)") (class "Default")
      (node (ref "C14") (pin "1") (pinfunction "1_1") (pintype "passive"))
      (node (ref "U3") (pin "6") (pinfunction "OSC2_6") (pintype "bidirectional"))
      (node (ref "Y2") (pin "1") (pinfunction "1_1") (pintype "bidirectional"))
    )
    (net (code "49") (name "Net-(U3-RXCAN)") (class "Default")
      (node (ref "U3") (pin "20") (pinfunction "RXCAN_20") (pintype "bidirectional"))
      (node (ref "U6") (pin "4") (pinfunction "RXD_4") (pintype "bidirectional"))
    )
    (net (code "50") (name "Net-(U3-TXCAN)") (class "Default")
      (node (ref "U3") (pin "19") (pinfunction "TXCAN_19") (pintype "bidirectional"))
      (node (ref "U6") (pin "1") (pinfunction "TXD_1") (pintype "bidirectional"))
    )
    (net (code "51") (name "Net-(U3-~{RESET})") (class "Default")
      (node (ref "R8") (pin "1") (pinfunction "1_1") (pintype "passive"))
      (node (ref "U3") (pin "17") (pinfunction "~{RESET}_17") (pintype "bidirectional"))
    )
    (net (code "52") (name "Net-(U3-~{RX1BF})") (class "Default")
      (node (ref "R4") (pin "2") (pinfunction "2_2") (pintype "passive"))
      (node (ref "U3") (pin "9") (pinfunction "~{RX1BF}_9") (pintype "bidirectional"))
      (node (ref "U6") (pin "8") (pinfunction "S_8") (pintype "bidirectional"))
    )
    (net (code "53") (name "Net-(U4-RXCAN)") (class "Default")
      (node (ref "U4") (pin "20") (pinfunction "RXCAN_20") (pintype "bidirectional"))
      (node (ref "U7") (pin "4") (pinfunction "RXD_4") (pintype "bidirectional"))
    )
    (net (code "54") (name "Net-(U4-TXCAN)") (class "Default")
      (node (ref "U4") (pin "19") (pinfunction "TXCAN_19") (pintype "bidirectional"))
      (node (ref "U7") (pin "1") (pinfunction "TXD_1") (pintype "bidirectional"))
    )
    (net (code "55") (name "Net-(U4-~{RESET})") (class "Default")
      (node (ref "R7") (pin "1") (pinfunction "1_1") (pintype "passive"))
      (node (ref "U4") (pin "17") (pinfunction "~{RESET}_17") (pintype "bidirectional"))
    )
    (net (code "56") (name "Net-(U4-~{RX1BF})") (class "Default")
      (node (ref "R5") (pin "2") (pinfunction "2_2") (pintype "passive"))
      (node (ref "U4") (pin "9") (pinfunction "~{RX1BF}_9") (pintype "bidirectional"))
      (node (ref "U7") (pin "8") (pinfunction "S_8") (pintype "bidirectional"))
    )
    (net (code "57") (name "Net-(U5-RXCAN)") (class "Default")
      (node (ref "U5") (pin "20") (pinfunction "RXCAN_20") (pintype "bidirectional"))
      (node (ref "U8") (pin "4") (pinfunction "RXD_4") (pintype "bidirectional"))
    )
    (net (code "58") (name "Net-(U5-TXCAN)") (class "Default")
      (node (ref "U5") (pin "19") (pinfunction "TXCAN_19") (pintype "bidirectional"))
      (node (ref "U8") (pin "1") (pinfunction "TXD_1") (pintype "bidirectional"))
    )
    (net (code "59") (name "Net-(U5-~{RESET})") (class "Default")
      (node (ref "R9") (pin "1") (pinfunction "1_1") (pintype "passive"))
      (node (ref "U5") (pin "17") (pinfunction "~{RESET}_17") (pintype "bidirectional"))
    )
    (net (code "60") (name "Net-(U5-~{RX1BF})") (class "Default")
      (node (ref "R6") (pin "2") (pinfunction "2_2") (pintype "passive"))
      (node (ref "U5") (pin "9") (pinfunction "~{RX1BF}_9") (pintype "bidirectional"))
      (node (ref "U8") (pin "8") (pinfunction "S_8") (pintype "bidirectional"))
    )
    (net (code "61") (name "Net-(U11-VBUS)") (class "Default")
      (node (ref "R11") (pin "1") (pinfunction "1_1") (pintype "passive"))
      (node (ref "R12") (pin "2") (pinfunction "2_2") (pintype "passive"))
      (node (ref "U11") (pin "8") (pinfunction "VBUS_8") (pintype "bidirectional"))
    )
    (net (code "62") (name "Net-(U11-VPP)") (class "Default")
      (node (ref "C31") (pin "1") (pinfunction "1_1") (pintype "passive"))
      (node (ref "U11") (pin "16") (pinfunction "VPP_16") (pintype "bidirectional"))
    )
    (net (code "63") (name "Net-(U11-~{RST})") (class "Default")
      (node (ref "R10") (pin "1") (pinfunction "1_1") (pintype "passive"))
      (node (ref "U11") (pin "9") (pinfunction "~{RST}_9") (pintype "bidirectional"))
    )
    (net (code "64") (name "PROGRAM") (class "Default")
      (node (ref "S1") (pin "2") (pinfunction "3_2") (pintype "passive"))
      (node (ref "U1") (pin "23") (pinfunction "GPIO00*/ADC2_CH1/TOUCH1/RTC_GPIO11/CLK_OUT1/EMAC_TX_CLK_23") (pintype "bidirectional"))
    )
    (net (code "65") (name "RX") (class "Default")
      (node (ref "U1") (pin "40") (pinfunction "GPIO01/U0RXD*/CLK_OUT2_40") (pintype "bidirectional"))
      (node (ref "U11") (pin "21") (pinfunction "TXD_21") (pintype "bidirectional"))
    )
    (net (code "66") (name "SCK") (class "Default")
      (node (ref "U1") (pin "35") (pinfunction "GPIO18*/VSPICLK/HS1_DATA7_35") (pintype "bidirectional"))
      (node (ref "U3") (pin "12") (pinfunction "SCK_12") (pintype "bidirectional"))
      (node (ref "U4") (pin "12") (pinfunction "SCK_12") (pintype "bidirectional"))
      (node (ref "U5") (pin "12") (pinfunction "SCK_12") (pintype "bidirectional"))
    )
    (net (code "67") (name "TX") (class "Default")
      (node (ref "U1") (pin "41") (pinfunction "GPIO03/U0TXD*/CLK_OUT3/EMAC_RXD2_41") (pintype "bidirectional"))
      (node (ref "U11") (pin "20") (pinfunction "RXD_20") (pintype "bidirectional"))
    )
    (net (code "68") (name "VBUS") (class "Default")
      (node (ref "D1") (pin "A") (pinfunction "A_A") (pintype "bidirectional"))
      (node (ref "J2") (pin "1") (pinfunction "VBUS_1") (pintype "bidirectional"))
      (node (ref "R11") (pin "2") (pinfunction "2_2") (pintype "passive"))
    )
    (net (code "69") (name "unconnected-(J2-ID-Pad4)") (class "Default")
      (node (ref "J2") (pin "4") (pinfunction "ID_4") (pintype "bidirectional"))
    )
    (net (code "70") (name "unconnected-(U1-GPIO02*{slash}ADC2_CH2{slash}TOUCH2{slash}RTC_GPIO12{slash}HSPIWP{slash}HS2_DATA0{slash}SD_DATA0-Pad22)") (class "Default")
      (node (ref "U1") (pin "22") (pinfunction "GPIO02*/ADC2_CH2/TOUCH2/RTC_GPIO12/HSPIWP/HS2_DATA0/SD_DATA0_22") (pintype "bidirectional"))
    )
    (net (code "71") (name "unconnected-(U1-GPIO05*{slash}VSPICSC0{slash}HS1_DATA6{slash}EMAC_RX_CLK-Pad34)") (class "Default")
      (node (ref "U1") (pin "34") (pinfunction "GPIO05*/VSPICSC0/HS1_DATA6/EMAC_RX_CLK_34") (pintype "bidirectional"))
    )
    (net (code "72") (name "unconnected-(U1-GPIO13{slash}MTCK*{slash}ADC2_CH4{slash}TOUCH4{slash}RTC_GPIO14{slash}HSPID{slash}HS2_DATA3{slash}SD_DATA3{slash}EMAC_RX_ER-Pad20)") (class "Default")
      (node (ref "U1") (pin "20") (pinfunction "GPIO13/MTCK*/ADC2_CH4/TOUCH4/RTC_GPIO14/HSPID/HS2_DATA3/SD_DATA3/EMAC_RX_ER_20") (pintype "bidirectional"))
    )
    (net (code "73") (name "unconnected-(U1-GPIO15{slash}MTDO*{slash}ADC2_CH3{slash}TOUCH3{slash}RTC_GPIO13{slash}HSPICS0{slash}HS2_CMD{slash}SD_CMD{slash}EMAC_RXD3-Pad21)") (class "Default")
      (node (ref "U1") (pin "21") (pinfunction "GPIO15/MTDO*/ADC2_CH3/TOUCH3/RTC_GPIO13/HSPICS0/HS2_CMD/SD_CMD/EMAC_RXD3_21") (pintype "bidirectional"))
    )
    (net (code "74") (name "unconnected-(U1-GPIO17*{slash}HS1_DATA5{slash}U2TXD{slash}EMAC_CLK_OUT_180-Pad27)") (class "Default")
      (node (ref "U1") (pin "27") (pinfunction "GPIO17*/HS1_DATA5/U2TXD/EMAC_CLK_OUT_180_27") (pintype "bidirectional"))
    )
    (net (code "75") (name "unconnected-(U1-GPIO21*{slash}VSPIHD{slash}EMAC_TX_EN-Pad42)") (class "Default")
      (node (ref "U1") (pin "42") (pinfunction "GPIO21*/VSPIHD/EMAC_TX_EN_42") (pintype "bidirectional"))
    )
    (net (code "76") (name "unconnected-(U1-GPIO22*{slash}VSPIWP{slash}U0RTS{slash}EMAC_TXD1-Pad39)") (class "Default")
      (node (ref "U1") (pin "39") (pinfunction "GPIO22*/VSPIWP/U0RTS/EMAC_TXD1_39") (pintype "bidirectional"))
    )
    (net (code "77") (name "unconnected-(U1-GPIO34{slash}VDET_1*{slash}ADC1_CH6{slash}RTC_GPIO4-Pad10)") (class "Default")
      (node (ref "U1") (pin "10") (pinfunction "GPIO34/VDET_1*/ADC1_CH6/RTC_GPIO4_10") (pintype "bidirectional"))
    )
    (net (code "78") (name "unconnected-(U1-GPIO35{slash}VDET_2*{slash}ADC1_CH7{slash}RTC_GIOP5-Pad11)") (class "Default")
      (node (ref "U1") (pin "11") (pinfunction "GPIO35/VDET_2*/ADC1_CH7/RTC_GIOP5_11") (pintype "bidirectional"))
    )
    (net (code "79") (name "unconnected-(U1-GPIO36{slash}SENSOR_VP*{slash}ADC_PRE_AMP{slash}ADC1_CH0{slash}RTC_GPIO0-Pad5)") (class "Default")
      (node (ref "U1") (pin "5") (pinfunction "GPIO36/SENSOR_VP*/ADC_PRE_AMP/ADC1_CH0/RTC_GPIO0_5") (pintype "bidirectional"))
    )
    (net (code "80") (name "unconnected-(U1-GPIO37{slash}SENSOR_CAPP*{slash}ADC_PRE_AMP{slash}ADC1_CH1{slash}RTC_GPIO1-Pad6)") (class "Default")
      (node (ref "U1") (pin "6") (pinfunction "GPIO37/SENSOR_CAPP*/ADC_PRE_AMP/ADC1_CH1/RTC_GPIO1_6") (pintype "bidirectional"))
    )
    (net (code "81") (name "unconnected-(U1-GPIO39{slash}SENSOR_VN*{slash}ADC_PRE_AMP{slash}ADC1_CH3{slash}RTC_GPIO3-Pad8)") (class "Default")
      (node (ref "U1") (pin "8") (pinfunction "GPIO39/SENSOR_VN*/ADC_PRE_AMP/ADC1_CH3/RTC_GPIO3_8") (pintype "bidirectional"))
    )
    (net (code "82") (name "unconnected-(U3-~{RX0BF}-Pad10)") (class "Default")
      (node (ref "U3") (pin "10") (pinfunction "~{RX0BF}_10") (pintype "bidirectional"))
    )
    (net (code "83") (name "unconnected-(U3-~{TX0RTS}-Pad2)") (class "Default")
      (node (ref "U3") (pin "2") (pinfunction "~{TX0RTS}_2") (pintype "bidirectional"))
    )
    (net (code "84") (name "unconnected-(U3-~{TX1RTS}-Pad3)") (class "Default")
      (node (ref "U3") (pin "3") (pinfunction "~{TX1RTS}_3") (pintype "bidirectional"))
    )
    (net (code "85") (name "unconnected-(U3-~{TX2RTS}-Pad5)") (class "Default")
      (node (ref "U3") (pin "5") (pinfunction "~{TX2RTS}_5") (pintype "bidirectional"))
    )
    (net (code "86") (name "unconnected-(U4-OSC1-Pad7)") (class "Default")
      (node (ref "U4") (pin "7") (pinfunction "OSC1_7") (pintype "bidirectional"))
    )
    (net (code "87") (name "unconnected-(U4-OSC2-Pad6)") (class "Default")
      (node (ref "U4") (pin "6") (pinfunction "OSC2_6") (pintype "bidirectional"))
    )
    (net (code "88") (name "unconnected-(U4-~{RX0BF}-Pad10)") (class "Default")
      (node (ref "U4") (pin "10") (pinfunction "~{RX0BF}_10") (pintype "bidirectional"))
    )
    (net (code "89") (name "unconnected-(U4-~{TX0RTS}-Pad2)") (class "Default")
      (node (ref "U4") (pin "2") (pinfunction "~{TX0RTS}_2") (pintype "bidirectional"))
    )
    (net (code "90") (name "unconnected-(U4-~{TX1RTS}-Pad3)") (class "Default")
      (node (ref "U4") (pin "3") (pinfunction "~{TX1RTS}_3") (pintype "bidirectional"))
    )
    (net (code "91") (name "unconnected-(U4-~{TX2RTS}-Pad5)") (class "Default")
      (node (ref "U4") (pin "5") (pinfunction "~{TX2RTS}_5") (pintype "bidirectional"))
    )
    (net (code "92") (name "unconnected-(U5-OSC1-Pad7)") (class "Default")
      (node (ref "U5") (pin "7") (pinfunction "OSC1_7") (pintype "bidirectional"))
    )
    (net (code "93") (name "unconnected-(U5-OSC2-Pad6)") (class "Default")
      (node (ref "U5") (pin "6") (pinfunction "OSC2_6") (pintype "bidirectional"))
    )
    (net (code "94") (name "unconnected-(U5-~{RX0BF}-Pad10)") (class "Default")
      (node (ref "U5") (pin "10") (pinfunction "~{RX0BF}_10") (pintype "bidirectional"))
    )
    (net (code "95") (name "unconnected-(U5-~{TX0RTS}-Pad2)") (class "Default")
      (node (ref "U5") (pin "2") (pinfunction "~{TX0RTS}_2") (pintype "bidirectional"))
    )
    (net (code "96") (name "unconnected-(U5-~{TX1RTS}-Pad3)") (class "Default")
      (node (ref "U5") (pin "3") (pinfunction "~{TX1RTS}_3") (pintype "bidirectional"))
    )
    (net (code "97") (name "unconnected-(U5-~{TX2RTS}-Pad5)") (class "Default")
      (node (ref "U5") (pin "5") (pinfunction "~{TX2RTS}_5") (pintype "bidirectional"))
    )
    (net (code "98") (name "unconnected-(U9-PG-Pad8)") (class "Default")
      (node (ref "U9") (pin "8") (pinfunction "PG_8") (pintype "bidirectional"))
    )
    (net (code "99") (name "unconnected-(U10-PG-Pad8)") (class "Default")
      (node (ref "U10") (pin "8") (pinfunction "PG_8") (pintype "bidirectional"))
    )
    (net (code "100") (name "unconnected-(U11-CTS-Pad18)") (class "Default")
      (node (ref "U11") (pin "18") (pinfunction "CTS_18") (pintype "bidirectional"))
    )
    (net (code "101") (name "unconnected-(U11-DCD-Pad24)") (class "Default")
      (node (ref "U11") (pin "24") (pinfunction "DCD_24") (pintype "bidirectional"))
    )
    (net (code "102") (name "unconnected-(U11-DSR-Pad22)") (class "Default")
      (node (ref "U11") (pin "22") (pinfunction "DSR_22") (pintype "bidirectional"))
    )
    (net (code "103") (name "unconnected-(U11-DTR-Pad23)") (class "Default")
      (node (ref "U11") (pin "23") (pinfunction "DTR_23") (pintype "bidirectional"))
    )
    (net (code "104") (name "unconnected-(U11-GPIO0-Pad14)") (class "Default")
      (node (ref "U11") (pin "14") (pinfunction "GPIO0_14") (pintype "bidirectional"))
    )
    (net (code "105") (name "unconnected-(U11-GPIO1-Pad13)") (class "Default")
      (node (ref "U11") (pin "13") (pinfunction "GPIO1_13") (pintype "bidirectional"))
    )
    (net (code "106") (name "unconnected-(U11-GPIO2-Pad12)") (class "Default")
      (node (ref "U11") (pin "12") (pinfunction "GPIO2_12") (pintype "bidirectional"))
    )
    (net (code "107") (name "unconnected-(U11-GPIO3-Pad11)") (class "Default")
      (node (ref "U11") (pin "11") (pinfunction "GPIO3_11") (pintype "bidirectional"))
    )
    (net (code "108") (name "unconnected-(U11-RI-Pad1)") (class "Default")
      (node (ref "U11") (pin "1") (pinfunction "RI_1") (pintype "bidirectional"))
    )
    (net (code "109") (name "unconnected-(U11-RTS-Pad19)") (class "Default")
      (node (ref "U11") (pin "19") (pinfunction "RTS_19") (pintype "bidirectional"))
    )
    (net (code "110") (name "unconnected-(U11-SUSPEND-Pad17)") (class "Default")
      (node (ref "U11") (pin "17") (pinfunction "SUSPEND_17") (pintype "bidirectional"))
    )
    (net (code "111") (name "unconnected-(U11-~{SUSPEND}-Pad15)") (class "Default")
      (node (ref "U11") (pin "15") (pinfunction "~{SUSPEND}_15") (pintype "bidirectional"))
    )
  )
)
